# Memory_Card.net
KiCad netlist of a schematic drawn in EAGLE
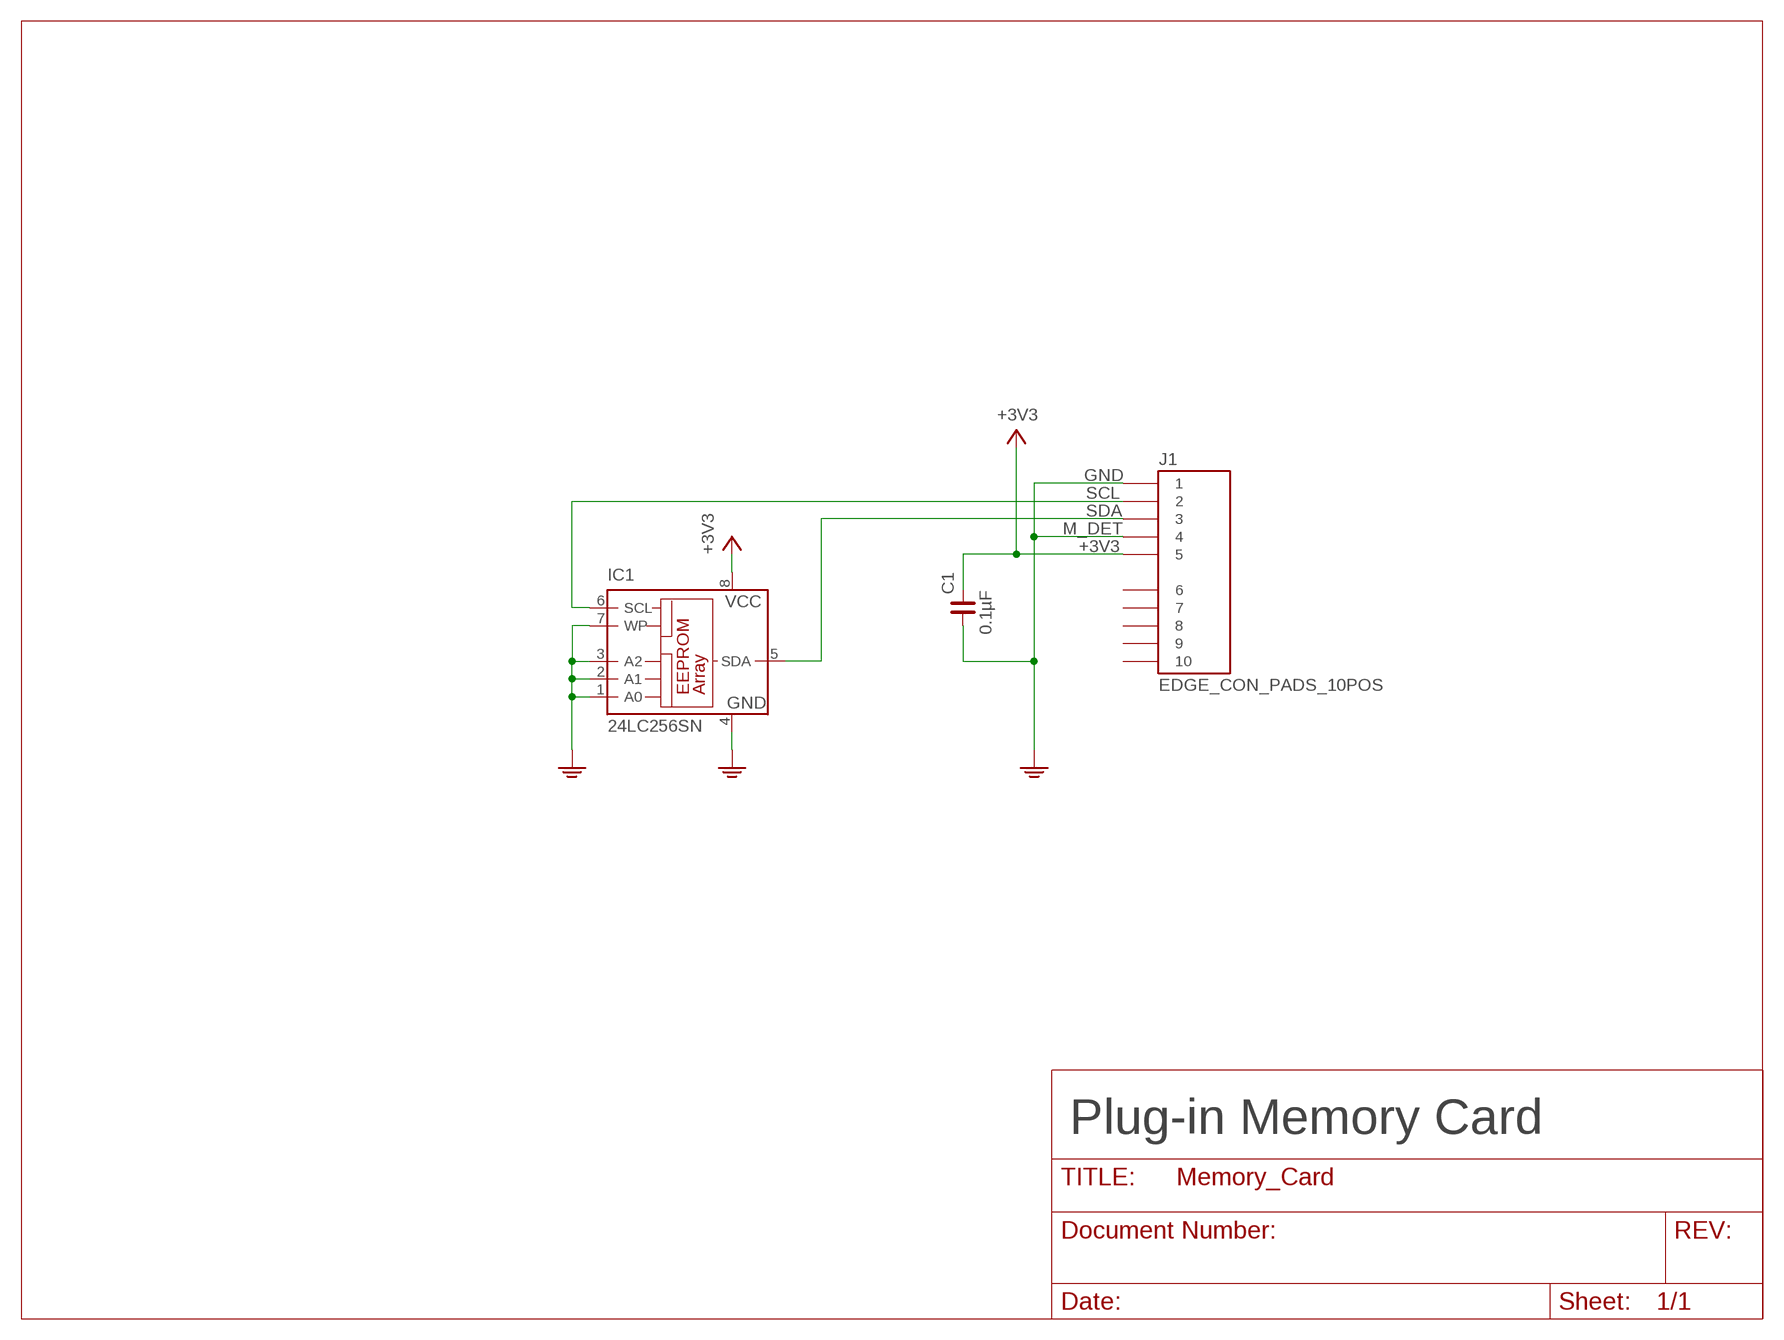
[diagram p0: schematic, sheet 1]

(export (version "E")
  (design (tool "Eeschema 10.0.6"))
  (components
    (comp (ref "C1")
      (value "0.1µF")
      (footprint "eagle-import:C0603")
      (libsource (lib "eagle-import") (part "C_0603"))
    )
    (comp (ref "IC1")
      (value "24LC256SN")
      (footprint "eagle-import:SO-08")
      (fields (field (name "MF") "MICROCHIP") (field (name "MPN") "24LC256-I/SN"))
      (libsource (lib "eagle-import") (part "24SNLC256"))
    )
    (comp (ref "J1")
      (value "EDGE_CON_PADS_10POS")
      (footprint "eagle-import:EDGE_CON_PADS")
      (libsource (lib "eagle-import") (part "EDGE_CON_PADS_10POS"))
    )
  )
  (nets
    (net (code "1") (name "+3V3") (class "Default")
      (node (ref "C1") (pin "2") (pinfunction "2_2") (pintype "passive"))
      (node (ref "IC1") (pin "8") (pinfunction "VCC_8") (pintype "power_in"))
      (node (ref "J1") (pin "5") (pinfunction "5_5") (pintype "passive"))
    )
    (net (code "2") (name "/SCL") (class "Default")
      (node (ref "IC1") (pin "6") (pinfunction "SCL_6") (pintype "input"))
      (node (ref "J1") (pin "2") (pinfunction "2_2") (pintype "passive"))
    )
    (net (code "3") (name "/SDA") (class "Default")
      (node (ref "IC1") (pin "5") (pinfunction "SDA_5") (pintype "bidirectional"))
      (node (ref "J1") (pin "3") (pinfunction "3_3") (pintype "passive"))
    )
    (net (code "4") (name "GND") (class "Default")
      (node (ref "C1") (pin "1") (pinfunction "1_1") (pintype "passive"))
      (node (ref "IC1") (pin "1") (pinfunction "A0_1") (pintype "input"))
      (node (ref "IC1") (pin "2") (pinfunction "A1_2") (pintype "input"))
      (node (ref "IC1") (pin "3") (pinfunction "A2_3") (pintype "input"))
      (node (ref "IC1") (pin "4") (pinfunction "GND_4") (pintype "power_in"))
      (node (ref "IC1") (pin "7") (pinfunction "WP_7") (pintype "input"))
      (node (ref "J1") (pin "1") (pinfunction "1_1") (pintype "passive"))
      (node (ref "J1") (pin "4") (pinfunction "4_4") (pintype "passive"))
    )
    (net (code "5") (name "unconnected-(J1-Pad6)") (class "Default")
      (node (ref "J1") (pin "6") (pinfunction "6_6") (pintype "passive"))
    )
    (net (code "6") (name "unconnected-(J1-Pad7)") (class "Default")
      (node (ref "J1") (pin "7") (pinfunction "7_7") (pintype "passive"))
    )
    (net (code "7") (name "unconnected-(J1-Pad8)") (class "Default")
      (node (ref "J1") (pin "8") (pinfunction "8_8") (pintype "passive"))
    )
    (net (code "8") (name "unconnected-(J1-Pad9)") (class "Default")
      (node (ref "J1") (pin "9") (pinfunction "9_9") (pintype "passive"))
    )
    (net (code "9") (name "unconnected-(J1-Pad10)") (class "Default")
      (node (ref "J1") (pin "10") (pinfunction "10_10") (pintype "passive"))
    )
  )
)
